# Regulator.net
KiCad netlist of a schematic drawn in Altium Designer
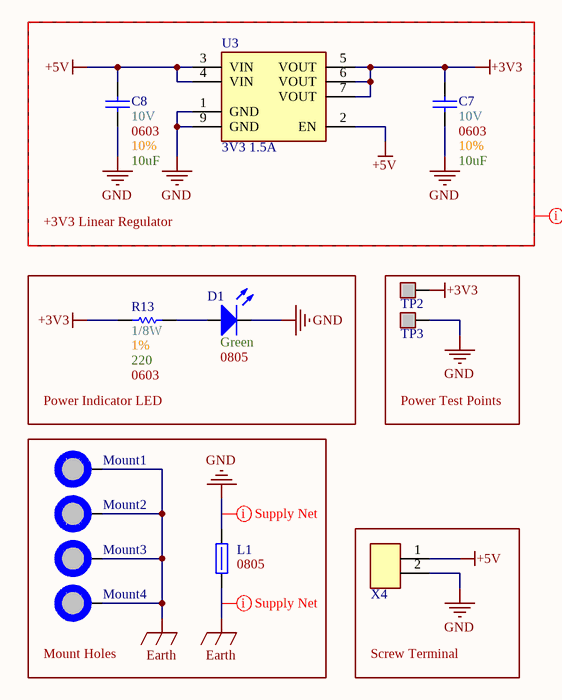
[diagram p0: Regulator.SchDoc]

(export (version "E")
  (design (tool "Eeschema 10.0.6"))
  (components
    (comp (ref "C7")
      (value "[Cap] 0603 10uF 10% 10V")
      (footprint "[Cap] SMD 0603")
      (description "CL10A106KP8NNNC")
      (fields
        (field (name "MAX VOLTAGE") "10V")
        (field (name "SIZE PACKAGE") "0603")
        (field (name "TOLERANCE") "10%")
        (field (name "CAPACITANCE") "10uF")
      )
      (libsource (lib "Capacitors") (part "[Cap] 0603 10uF 10% 10V"))
    )
    (comp (ref "C8")
      (value "[Cap] 0603 10uF 10% 10V")
      (footprint "[Cap] SMD 0603")
      (description "CL10A106KP8NNNC")
      (fields
        (field (name "MAX VOLTAGE") "10V")
        (field (name "SIZE PACKAGE") "0603")
        (field (name "TOLERANCE") "10%")
        (field (name "CAPACITANCE") "10uF")
      )
      (libsource (lib "Capacitors") (part "[Cap] 0603 10uF 10% 10V"))
    )
    (comp (ref "D1")
      (value "[LED] SMD 0805 Green")
      (footprint "[LED] SMD 0805")
      (description "LG R971-KN-1-0-20-R18")
      (fields (field (name "COLOR") "Green") (field (name "SIZE PACKAGE") "0805"))
      (libsource (lib "LEDs") (part "[LED] SMD 0805 Green"))
    )
    (comp (ref "L1")
      (value "652-MH2029-300Y")
      (footprint "[Ferrite] SMD 0805")
      (fields (field (name "SIZE PACKAGE") "0805"))
      (libsource (lib "Ferrite Beads") (part "[Ferrite] SMD 0805 3A 30ohm"))
    )
    (comp (ref "Mount1")
      (value "M3 Mount Hole")
      (footprint "[Mount] M3 Mount Hole")
      (description "Place at least 4.5mm from board edge. Plated.")
      (libsource (lib "RADM Connectors") (part "[Mount] M3 Mount Hole"))
    )
    (comp (ref "Mount2")
      (value "M3 Mount Hole")
      (footprint "[Mount] M3 Mount Hole")
      (description "Place at least 4.5mm from board edge. Plated.")
      (libsource (lib "RADM Connectors") (part "[Mount] M3 Mount Hole"))
    )
    (comp (ref "Mount3")
      (value "M3 Mount Hole")
      (footprint "[Mount] M3 Mount Hole")
      (description "Place at least 4.5mm from board edge. Plated.")
      (libsource (lib "RADM Connectors") (part "[Mount] M3 Mount Hole"))
    )
    (comp (ref "Mount4")
      (value "M3 Mount Hole")
      (footprint "[Mount] M3 Mount Hole")
      (description "Place at least 4.5mm from board edge. Plated.")
      (libsource (lib "RADM Connectors") (part "[Mount] M3 Mount Hole"))
    )
    (comp (ref "R13")
      (value "[220] SMD 0603 1% 1/10W")
      (footprint "[Res] SMD 0603")
      (description "CRGCQ0805F220R")
      (fields
        (field (name "WATTAGE") "1/8W")
        (field (name "TOLERANCE") "1%")
        (field (name "RESISTANCE") "220")
        (field (name "SIZE PACKAGE") "0603")
      )
      (libsource (lib "Resistors") (part "[220] SMD 0603 1% 1/10W"))
    )
    (comp (ref "TP2")
      (value "[THM] Thru-Hole")
      (footprint "[THM] White")
      (description "5012")
      (libsource (lib "Test Points") (part "[THM] Thru-Hole"))
    )
    (comp (ref "TP3")
      (value "[THM] Thru-Hole")
      (footprint "[THM] White")
      (description "5012")
      (libsource (lib "Test Points") (part "[THM] Thru-Hole"))
    )
    (comp (ref "U3")
      (value "3V3 1.5A")
      (footprint "[Linear] 3V3 1.5A")
      (description "AP7362A-33SP-13")
      (libsource (lib "Voltage Regulators") (part "[Linear] 3V3 1.5A"))
    )
    (comp (ref "X4")
      (value "2pin Screw Terminal")
      (footprint "[Screw Terminal] 2pin 5mm")
      (description "TB002-500-02BE")
      (libsource (lib "Connectors") (part "[Screw Terminal] 2pin"))
    )
  )
  (nets
    (net (code "1") (name "+3V3") (class "Default")
      (node (ref "C7") (pin "2") (pinfunction "2_2") (pintype "passive"))
      (node (ref "R13") (pin "1") (pinfunction "1_1") (pintype "passive"))
      (node (ref "TP2") (pin "1") (pinfunction "1_1") (pintype "passive"))
      (node (ref "U3") (pin "5") (pinfunction "VOUT_5") (pintype "passive"))
      (node (ref "U3") (pin "6") (pinfunction "VOUT_6") (pintype "passive"))
      (node (ref "U3") (pin "7") (pinfunction "VOUT_7") (pintype "passive"))
    )
    (net (code "2") (name "+5V") (class "Default")
      (node (ref "C8") (pin "2") (pinfunction "2_2") (pintype "passive"))
      (node (ref "U3") (pin "2") (pinfunction "EN_2") (pintype "passive"))
      (node (ref "U3") (pin "3") (pinfunction "VIN_3") (pintype "passive"))
      (node (ref "U3") (pin "4") (pinfunction "VIN_4") (pintype "passive"))
      (node (ref "X4") (pin "1") (pintype "power_in"))
    )
    (net (code "3") (name "Earth") (class "Default")
      (node (ref "L1") (pin "1") (pinfunction "1_1") (pintype "passive"))
      (node (ref "Mount1") (pin "1") (pintype "power_in"))
      (node (ref "Mount2") (pin "1") (pintype "power_in"))
      (node (ref "Mount3") (pin "1") (pintype "power_in"))
      (node (ref "Mount4") (pin "1") (pintype "power_in"))
    )
    (net (code "4") (name "GND") (class "Default")
      (node (ref "C7") (pin "1") (pinfunction "1_1") (pintype "passive"))
      (node (ref "C8") (pin "1") (pinfunction "1_1") (pintype "passive"))
      (node (ref "D1") (pin "2") (pinfunction "Cathode_2") (pintype "passive"))
      (node (ref "L1") (pin "2") (pinfunction "2_2") (pintype "passive"))
      (node (ref "TP3") (pin "1") (pinfunction "1_1") (pintype "passive"))
      (node (ref "U3") (pin "1") (pinfunction "GND_1") (pintype "passive"))
      (node (ref "U3") (pin "9") (pinfunction "GND_9") (pintype "passive"))
      (node (ref "X4") (pin "2") (pintype "power_in"))
    )
    (net (code "5") (name "Net-(D1-Anode)") (class "Default")
      (node (ref "D1") (pin "1") (pinfunction "Anode_1") (pintype "passive"))
      (node (ref "R13") (pin "2") (pinfunction "2_2") (pintype "passive"))
    )
  )
)
